# DriveMoteur.net
KiCad netlist of a schematic drawn in Altium Designer
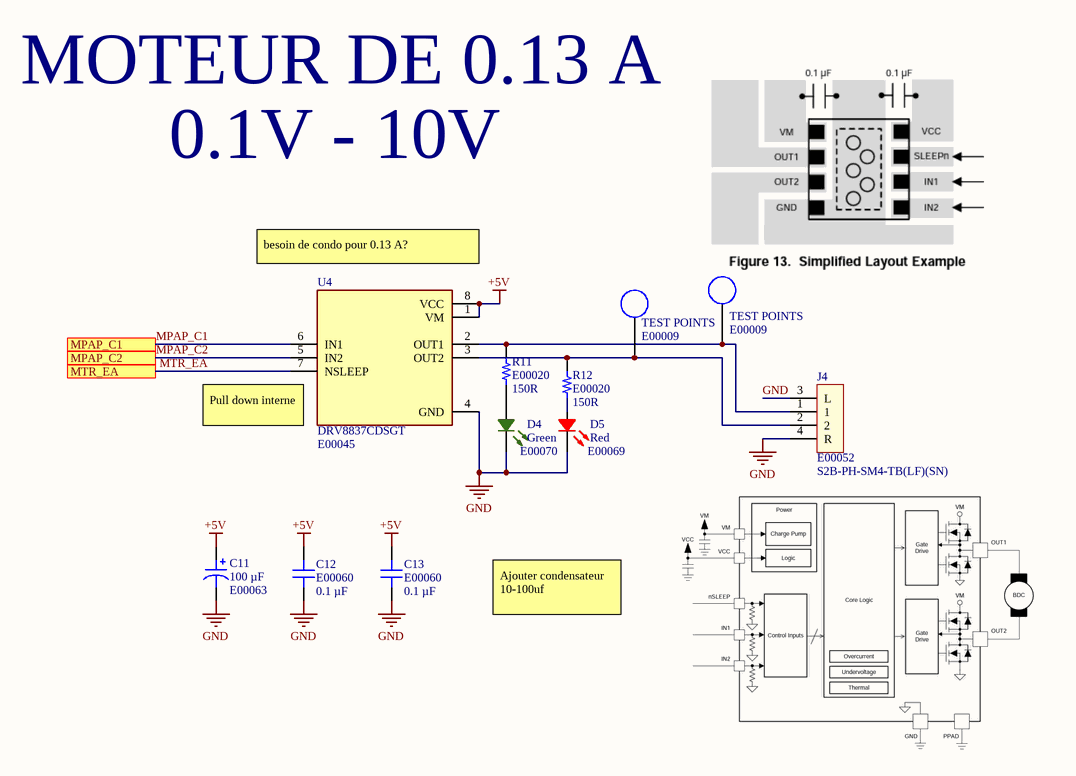
[diagram p0: DriveMoteur.SchDoc]

(export (version "E")
  (design (tool "Eeschema 10.0.6"))
  (components
    (comp (ref "C11")
      (value "100 µF")
      (footprint "CAP ALSMD ELEC 8.3MM H10.5MM")
      (description "CAP ALUM 100UF 20% 50V SMD")
      (fields
        (field (name "MANUFACTURER") "Nichicon")
        (field (name "TOLERANCE") "±20%")
        (field (name "ADAM INVENTORY NUMBER 1") "E00063")
      )
      (libsource (lib "ADAM LIBRARY") (part "CAP ALUM 100UF 20% 50V SMD"))
    )
    (comp (ref "C12")
      (value "0.1 µF")
      (footprint "CAP 0603")
      (description "CAP CER 0.1UF 50V X7R 0603")
      (fields
        (field (name "MANUFACTURER") "KEMET")
        (field (name "TOLERANCE") "±10%")
        (field (name "ADAM INVENTORY NUMBER 1") "E00060")
      )
      (libsource (lib "ADAM LIBRARY") (part "CAP CER 0.1UF 50V X7R 0603"))
    )
    (comp (ref "C13")
      (value "0.1 µF")
      (footprint "CAP 0603")
      (description "CAP CER 0.1UF 50V X7R 0603")
      (fields
        (field (name "MANUFACTURER") "KEMET")
        (field (name "TOLERANCE") "±10%")
        (field (name "ADAM INVENTORY NUMBER 1") "E00060")
      )
      (libsource (lib "ADAM LIBRARY") (part "CAP CER 0.1UF 50V X7R 0603"))
    )
    (comp (ref "D4")
      (value "Green")
      (footprint "Green LED 0603")
      (description "LED GREEN 0603 SMD")
      (fields (field (name "MANUFACTURER") "Dialight") (field (name "ADAM INVENTORY NUMBER 1") "E00070"))
      (libsource (lib "ADAM LIBRARY") (part "0603 GREEN LED"))
    )
    (comp (ref "D5")
      (value "Red")
      (footprint "Red Led 0603")
      (description "0603 RED LED")
      (fields
        (field (name "MANUFACTURER") "American Bright Optoelectronics Corporation")
        (field (name "ADAM INVENTORY NUMBER 1") "E00069")
      )
      (libsource (lib "ADAM LIBRARY") (part "0603 RED LED"))
    )
    (comp (ref "J4")
      (value "CONN JST 2P SM 90DEG")
      (footprint "S2B-PH-SM4-TB_LF__SN")
      (description "CONN SM JST 2P")
      (fields
        (field (name "ADAM INVENTORY NUMBER 1") "E00052")
        (field (name "SUPPLIER PART NUMBER 1") "S2B-PH-SM4-TB(LF)(SN)")
        (field (name "COPYRIGHT") "Copyright (C) 2023 Ultra Librarian. All rights reserved.")
      )
      (libsource (lib "ADAM LIBRARY") (part "CONN JST 2P SM 90DEG"))
    )
    (comp (ref "R11")
      (value "150R")
      (footprint "RES 0603")
      (description "RES SMD 150 OHM 0.1% 1/8W 0603")
      (fields
        (field (name "MANUFACTURER") "Vishay Beyschlag")
        (field (name "TOLERANCE") "±0.1%")
        (field (name "ADAM INVENTORY NUMBER 1") "E00020")
      )
      (libsource (lib "ADAM LIBRARY") (part "RES SMD 150 OHM"))
    )
    (comp (ref "R12")
      (value "150R")
      (footprint "RES 0603")
      (description "RES SMD 150 OHM 0.1% 1/8W 0603")
      (fields
        (field (name "MANUFACTURER") "Vishay Beyschlag")
        (field (name "TOLERANCE") "±0.1%")
        (field (name "ADAM INVENTORY NUMBER 1") "E00020")
      )
      (libsource (lib "ADAM LIBRARY") (part "RES SMD 150 OHM"))
    )
    (comp (ref "T1")
      (value "TEST POINTS")
      (footprint "TEST POINTS")
      (description "RCWCTE TEST POINTS")
      (fields (field (name "ADAM INVENTORY NUMBER 1") "E00009"))
      (libsource (lib "ADAM LIBRARY") (part "TEST POINTS"))
    )
    (comp (ref "T2")
      (value "TEST POINTS")
      (footprint "TEST POINTS")
      (description "RCWCTE TEST POINTS")
      (fields (field (name "ADAM INVENTORY NUMBER 1") "E00009"))
      (libsource (lib "ADAM LIBRARY") (part "TEST POINTS"))
    )
    (comp (ref "U4")
      (value "DRV8837CDSGT")
      (footprint "SON50P200X200X80-9N")
      (description "Motor Driver NMOS PWM 8-WSON (2x2)")
      (fields (field (name "ADAM INVENTORY NUMBER 1") "E00045"))
      (libsource (lib "ADAM LIBRARY") (part "DRV8837CDSGT"))
    )
  )
  (nets
    (net (code "1") (name "+5V") (class "Default")
      (node (ref "C11") (pin "1") (pinfunction "1_1") (pintype "passive"))
      (node (ref "C12") (pin "2") (pinfunction "2_2") (pintype "passive"))
      (node (ref "C13") (pin "2") (pinfunction "2_2") (pintype "passive"))
      (node (ref "U4") (pin "1") (pinfunction "VM_1") (pintype "passive"))
      (node (ref "U4") (pin "8") (pinfunction "VCC_8") (pintype "passive"))
    )
    (net (code "2") (name "/MPAP_C1") (class "Default")
      (node (ref "U4") (pin "6") (pinfunction "IN1_6") (pintype "passive"))
    )
    (net (code "3") (name "/MPAP_C2") (class "Default")
      (node (ref "U4") (pin "5") (pinfunction "IN2_5") (pintype "passive"))
    )
    (net (code "4") (name "/MTR_EA") (class "Default")
      (node (ref "U4") (pin "7") (pinfunction "NSLEEP_7") (pintype "passive"))
    )
    (net (code "5") (name "GND") (class "Default")
      (node (ref "C11") (pin "2") (pinfunction "2_2") (pintype "passive"))
      (node (ref "C12") (pin "1") (pinfunction "1_1") (pintype "passive"))
      (node (ref "C13") (pin "1") (pinfunction "1_1") (pintype "passive"))
      (node (ref "D4") (pin "2") (pinfunction "2_2") (pintype "passive"))
      (node (ref "D5") (pin "2") (pinfunction "2_2") (pintype "passive"))
      (node (ref "J4") (pin "3") (pinfunction "L_3") (pintype "passive"))
      (node (ref "J4") (pin "4") (pinfunction "R_4") (pintype "passive"))
      (node (ref "U4") (pin "4") (pinfunction "GND_4") (pintype "passive"))
    )
    (net (code "6") (name "Net-(D4-Pad1)") (class "Default")
      (node (ref "D4") (pin "1") (pinfunction "1_1") (pintype "passive"))
      (node (ref "R11") (pin "1") (pinfunction "1_1") (pintype "passive"))
    )
    (net (code "7") (name "Net-(D5-Pad1)") (class "Default")
      (node (ref "D5") (pin "1") (pinfunction "1_1") (pintype "passive"))
      (node (ref "R12") (pin "1") (pinfunction "1_1") (pintype "passive"))
    )
    (net (code "8") (name "Net-(U4-OUT1)") (class "Default")
      (node (ref "J4") (pin "1") (pinfunction "1_1") (pintype "passive"))
      (node (ref "R11") (pin "2") (pinfunction "2_2") (pintype "passive"))
      (node (ref "T1") (pin "1") (pinfunction "1_1") (pintype "passive"))
      (node (ref "U4") (pin "2") (pinfunction "OUT1_2") (pintype "passive"))
    )
    (net (code "9") (name "Net-(U4-OUT2)") (class "Default")
      (node (ref "J4") (pin "2") (pinfunction "2_2") (pintype "passive"))
      (node (ref "R12") (pin "2") (pinfunction "2_2") (pintype "passive"))
      (node (ref "T2") (pin "1") (pinfunction "1_1") (pintype "passive"))
      (node (ref "U4") (pin "3") (pinfunction "OUT2_3") (pintype "passive"))
    )
  )
)
